# Connectors.net
KiCad netlist of a schematic drawn in Altium Designer
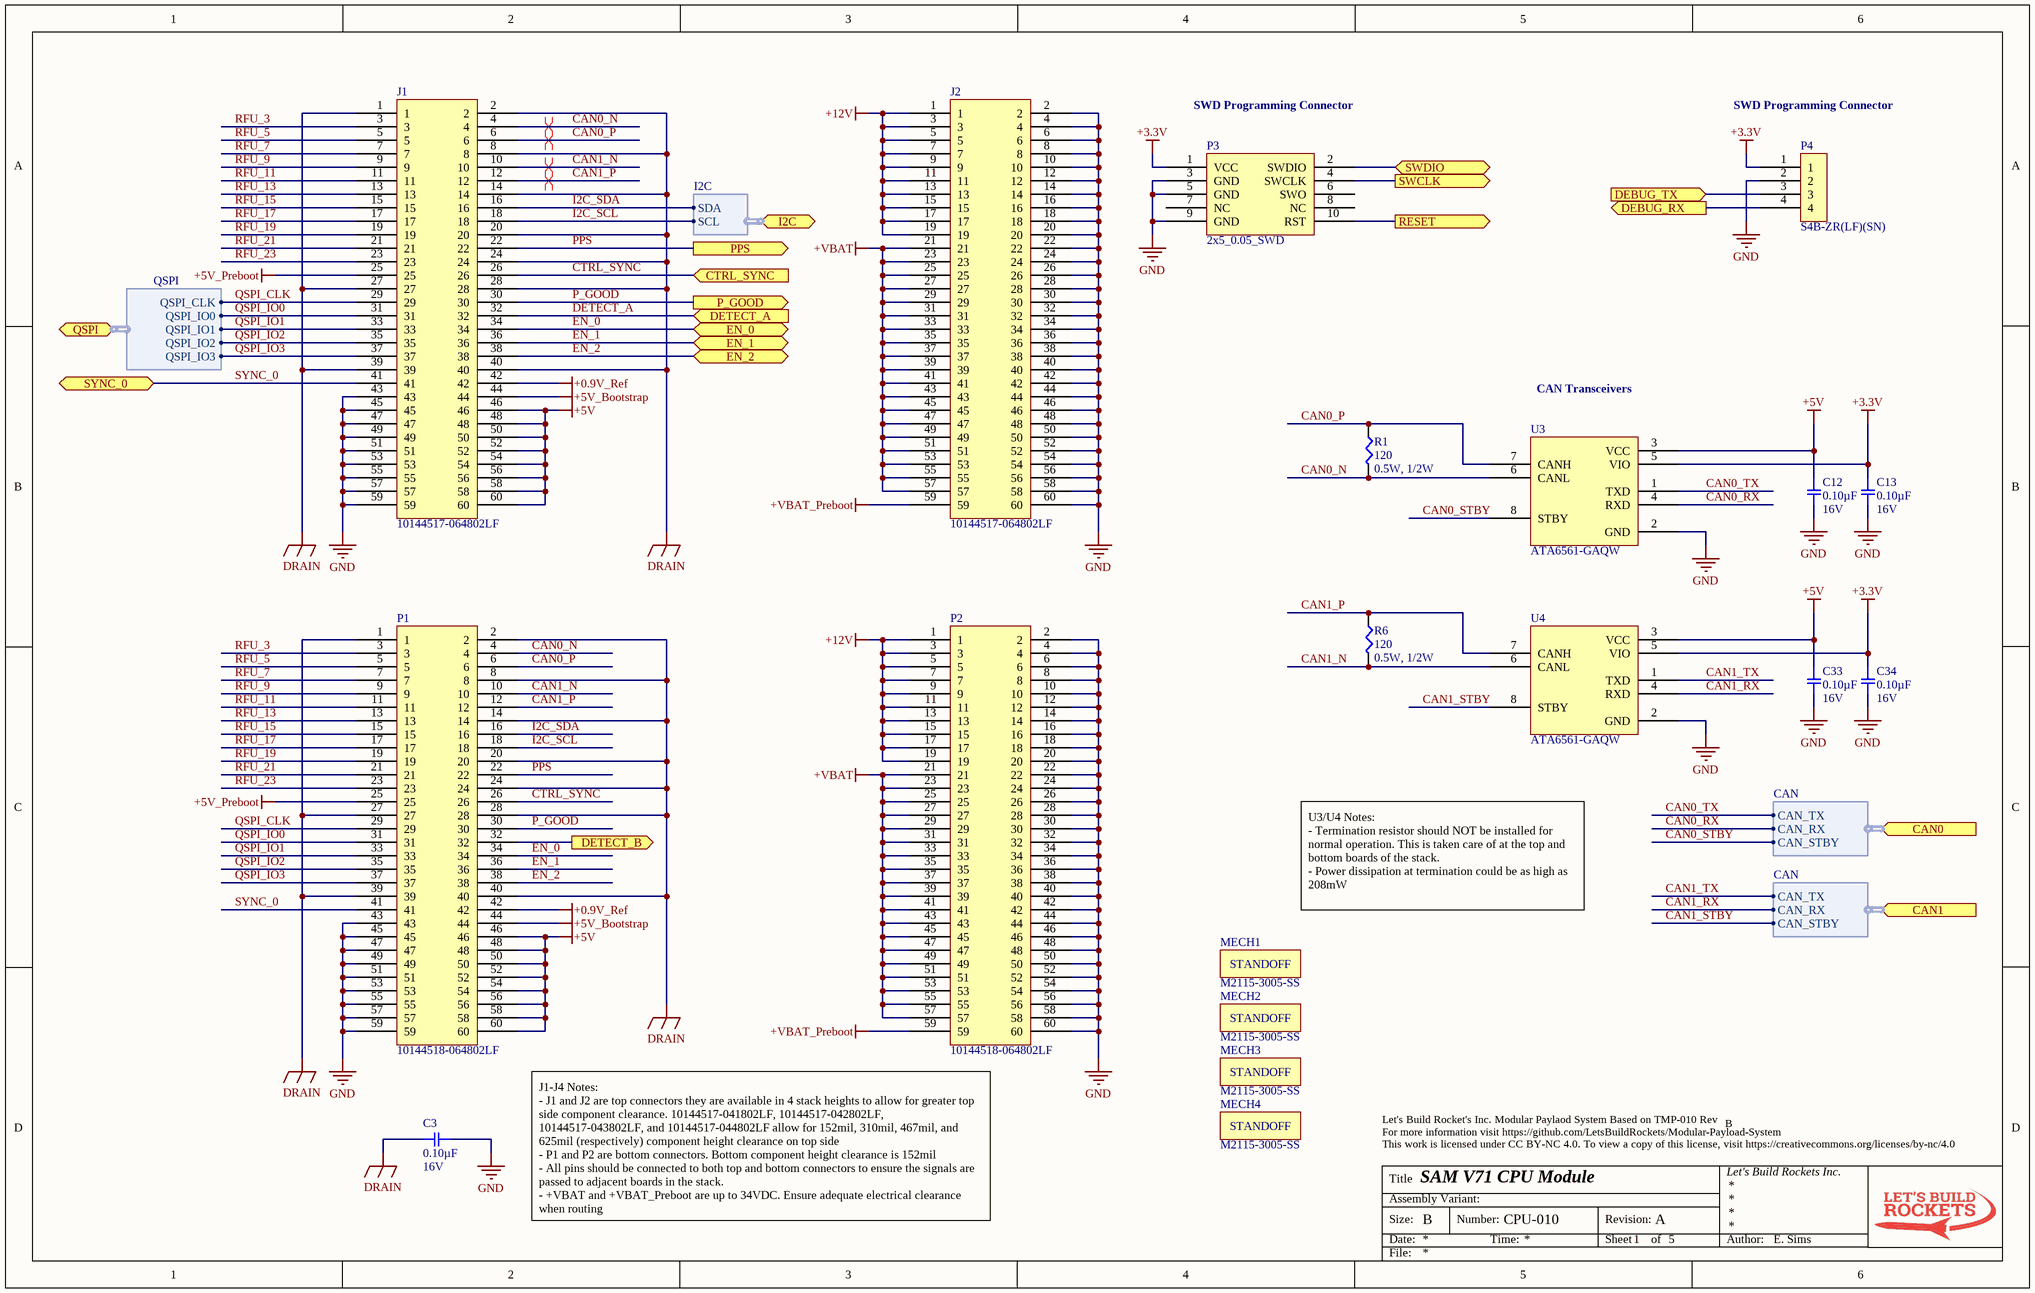
[diagram p0: Connectors.SchDoc]

(export (version "E")
  (design (tool "Eeschema 10.0.6"))
  (components
    (comp (ref "C3")
      (value "0.10µF")
      (footprint "SMD-0402C")
      (description "CAP CER 0.1UF 16V X7R 0402")
      (fields
        (field (name "DIGI-KEY PART NUMBER") "490-4759-1-ND")
        (field (name "PART NUMBER") "GCM155R71C104KA55D")
        (field (name "VOLTAGE") "16V")
      )
      (libsource (lib "capacitor_murata_0402") (part "GCM155R71C104KA55D"))
    )
    (comp (ref "C12")
      (value "0.10µF")
      (footprint "SMD-0402C")
      (description "CAP CER 0.1UF 16V X7R 0402")
      (fields
        (field (name "DIGI-KEY PART NUMBER") "490-4759-1-ND")
        (field (name "PART NUMBER") "GCM155R71C104KA55D")
        (field (name "VOLTAGE") "16V")
      )
      (libsource (lib "capacitor_murata_0402") (part "GCM155R71C104KA55D"))
    )
    (comp (ref "C13")
      (value "0.10µF")
      (footprint "SMD-0402C")
      (description "CAP CER 0.1UF 16V X7R 0402")
      (fields
        (field (name "DIGI-KEY PART NUMBER") "490-4759-1-ND")
        (field (name "PART NUMBER") "GCM155R71C104KA55D")
        (field (name "VOLTAGE") "16V")
      )
      (libsource (lib "capacitor_murata_0402") (part "GCM155R71C104KA55D"))
    )
    (comp (ref "C33")
      (value "0.10µF")
      (footprint "SMD-0402C")
      (description "CAP CER 0.1UF 16V X7R 0402")
      (fields
        (field (name "DIGI-KEY PART NUMBER") "490-4759-1-ND")
        (field (name "PART NUMBER") "GCM155R71C104KA55D")
        (field (name "VOLTAGE") "16V")
      )
      (libsource (lib "capacitor_murata_0402") (part "GCM155R71C104KA55D"))
    )
    (comp (ref "C34")
      (value "0.10µF")
      (footprint "SMD-0402C")
      (description "CAP CER 0.1UF 16V X7R 0402")
      (fields
        (field (name "DIGI-KEY PART NUMBER") "490-4759-1-ND")
        (field (name "PART NUMBER") "GCM155R71C104KA55D")
        (field (name "VOLTAGE") "16V")
      )
      (libsource (lib "capacitor_murata_0402") (part "GCM155R71C104KA55D"))
    )
    (comp (ref "J1")
      (value "10144517-064802LF")
      (footprint "10144517-064802LF")
      (libsource (lib "ModularPayload") (part "10144517-064802LF"))
    )
    (comp (ref "J2")
      (value "10144517-064802LF")
      (footprint "10144517-064802LF")
      (libsource (lib "ModularPayload") (part "10144517-064802LF"))
    )
    (comp (ref "MECH1")
      (value "M2115-3005-SS")
      (footprint "M2115-3005-SS")
      (libsource (lib "ModularPayload") (part "M2115-3005-SS"))
    )
    (comp (ref "MECH2")
      (value "M2115-3005-SS")
      (footprint "M2115-3005-SS")
      (libsource (lib "ModularPayload") (part "M2115-3005-SS"))
    )
    (comp (ref "MECH3")
      (value "M2115-3005-SS")
      (footprint "M2115-3005-SS")
      (libsource (lib "ModularPayload") (part "M2115-3005-SS"))
    )
    (comp (ref "MECH4")
      (value "M2115-3005-SS")
      (footprint "M2115-3005-SS")
      (libsource (lib "ModularPayload") (part "M2115-3005-SS"))
    )
    (comp (ref "P1")
      (value "10144518-064802LF")
      (footprint "10144518-064802LF")
      (libsource (lib "ModularPayload") (part "10144518-064802LF"))
    )
    (comp (ref "P2")
      (value "10144518-064802LF")
      (footprint "10144518-064802LF")
      (libsource (lib "ModularPayload") (part "10144518-064802LF"))
    )
    (comp (ref "P3")
      (value "2x5_0.05_SWD")
      (footprint "2x5_0.05_R")
      (libsource (lib "ModularPayload") (part "2x5_0.05_SWD"))
    )
    (comp (ref "P4")
      (value "S4B-ZR(LF)(SN)")
      (footprint "S4B-ZR(LF)(SN)")
      (libsource (lib "ModularPayload") (part "S4B-ZR(LF)(SN)"))
    )
    (comp (ref "R1")
      (value "120")
      (footprint "SMD-0805-RES")
      (description "RES SMD 120 OHM 5% 1/2W 0805")
      (fields
        (field (name "PART NUMBER") "ERJ-P6WJ121V")
        (field (name "DIGI-KEY PART NUMBER") "P16943CT-ND")
        (field (name "POWER (WATTS)") "0.5W, 1/2W")
      )
      (libsource (lib "Panasonic_ERJ_0805") (part "ERJ-P6WJ121V"))
    )
    (comp (ref "R6")
      (value "120")
      (footprint "SMD-0805-RES")
      (description "RES SMD 120 OHM 5% 1/2W 0805")
      (fields
        (field (name "PART NUMBER") "ERJ-P6WJ121V")
        (field (name "DIGI-KEY PART NUMBER") "P16943CT-ND")
        (field (name "POWER (WATTS)") "0.5W, 1/2W")
      )
      (libsource (lib "Panasonic_ERJ_0805") (part "ERJ-P6WJ121V"))
    )
    (comp (ref "U3")
      (value "ATA6561-GAQW")
      (footprint "SOIC127P600X175-8N")
      (libsource (lib "ModularPayload") (part "ATA6561-GAQW"))
    )
    (comp (ref "U4")
      (value "ATA6561-GAQW")
      (footprint "SOIC127P600X175-8N")
      (libsource (lib "ModularPayload") (part "ATA6561-GAQW"))
    )
  )
  (nets
    (net (code "4") (name "+0.9V_Ref") (class "Default")
      (node (ref "J1") (pin "42") (pinfunction "42_42") (pintype "passive"))
      (node (ref "P1") (pin "42") (pinfunction "42_42") (pintype "passive"))
    )
    (net (code "5") (name "+3.3V") (class "Default")
      (node (ref "C13") (pin "1") (pinfunction "1_1") (pintype "passive"))
      (node (ref "C34") (pin "1") (pinfunction "1_1") (pintype "passive"))
      (node (ref "P3") (pin "1") (pinfunction "VCC_1") (pintype "passive"))
      (node (ref "P4") (pin "1") (pinfunction "1_1") (pintype "passive"))
      (node (ref "U3") (pin "5") (pinfunction "VIO_5") (pintype "passive"))
      (node (ref "U4") (pin "5") (pinfunction "VIO_5") (pintype "passive"))
    )
    (net (code "6") (name "+5V") (class "Default")
      (node (ref "C12") (pin "1") (pinfunction "1_1") (pintype "passive"))
      (node (ref "C33") (pin "1") (pinfunction "1_1") (pintype "passive"))
      (node (ref "J1") (pin "46") (pinfunction "46_46") (pintype "passive"))
      (node (ref "J1") (pin "48") (pinfunction "48_48") (pintype "passive"))
      (node (ref "J1") (pin "50") (pinfunction "50_50") (pintype "passive"))
      (node (ref "J1") (pin "52") (pinfunction "52_52") (pintype "passive"))
      (node (ref "J1") (pin "54") (pinfunction "54_54") (pintype "passive"))
      (node (ref "J1") (pin "56") (pinfunction "56_56") (pintype "passive"))
      (node (ref "J1") (pin "58") (pinfunction "58_58") (pintype "passive"))
      (node (ref "J1") (pin "60") (pinfunction "60_60") (pintype "passive"))
      (node (ref "P1") (pin "46") (pinfunction "46_46") (pintype "passive"))
      (node (ref "P1") (pin "48") (pinfunction "48_48") (pintype "passive"))
      (node (ref "P1") (pin "50") (pinfunction "50_50") (pintype "passive"))
      (node (ref "P1") (pin "52") (pinfunction "52_52") (pintype "passive"))
      (node (ref "P1") (pin "54") (pinfunction "54_54") (pintype "passive"))
      (node (ref "P1") (pin "56") (pinfunction "56_56") (pintype "passive"))
      (node (ref "P1") (pin "58") (pinfunction "58_58") (pintype "passive"))
      (node (ref "P1") (pin "60") (pinfunction "60_60") (pintype "passive"))
      (node (ref "U3") (pin "3") (pinfunction "VCC_3") (pintype "passive"))
      (node (ref "U4") (pin "3") (pinfunction "VCC_3") (pintype "passive"))
    )
    (net (code "7") (name "+5V_Bootstrap") (class "Default")
      (node (ref "J1") (pin "44") (pinfunction "44_44") (pintype "passive"))
      (node (ref "P1") (pin "44") (pinfunction "44_44") (pintype "passive"))
    )
    (net (code "8") (name "+5V_Preboot") (class "Default")
      (node (ref "J1") (pin "25") (pinfunction "25_25") (pintype "passive"))
      (node (ref "P1") (pin "25") (pinfunction "25_25") (pintype "passive"))
    )
    (net (code "9") (name "+12V") (class "Default")
      (node (ref "J2") (pin "1") (pinfunction "1_1") (pintype "passive"))
      (node (ref "J2") (pin "11") (pinfunction "11_11") (pintype "passive"))
      (node (ref "J2") (pin "13") (pinfunction "13_13") (pintype "passive"))
      (node (ref "J2") (pin "15") (pinfunction "15_15") (pintype "passive"))
      (node (ref "J2") (pin "17") (pinfunction "17_17") (pintype "passive"))
      (node (ref "J2") (pin "19") (pinfunction "19_19") (pintype "passive"))
      (node (ref "J2") (pin "3") (pinfunction "3_3") (pintype "passive"))
      (node (ref "J2") (pin "5") (pinfunction "5_5") (pintype "passive"))
      (node (ref "J2") (pin "7") (pinfunction "7_7") (pintype "passive"))
      (node (ref "J2") (pin "9") (pinfunction "9_9") (pintype "passive"))
      (node (ref "P2") (pin "1") (pinfunction "1_1") (pintype "passive"))
      (node (ref "P2") (pin "11") (pinfunction "11_11") (pintype "passive"))
      (node (ref "P2") (pin "13") (pinfunction "13_13") (pintype "passive"))
      (node (ref "P2") (pin "15") (pinfunction "15_15") (pintype "passive"))
      (node (ref "P2") (pin "17") (pinfunction "17_17") (pintype "passive"))
      (node (ref "P2") (pin "19") (pinfunction "19_19") (pintype "passive"))
      (node (ref "P2") (pin "3") (pinfunction "3_3") (pintype "passive"))
      (node (ref "P2") (pin "5") (pinfunction "5_5") (pintype "passive"))
      (node (ref "P2") (pin "7") (pinfunction "7_7") (pintype "passive"))
      (node (ref "P2") (pin "9") (pinfunction "9_9") (pintype "passive"))
    )
    (net (code "10") (name "+VBAT") (class "Default")
      (node (ref "J2") (pin "21") (pinfunction "21_21") (pintype "passive"))
      (node (ref "J2") (pin "23") (pinfunction "23_23") (pintype "passive"))
      (node (ref "J2") (pin "25") (pinfunction "25_25") (pintype "passive"))
      (node (ref "J2") (pin "27") (pinfunction "27_27") (pintype "passive"))
      (node (ref "J2") (pin "29") (pinfunction "29_29") (pintype "passive"))
      (node (ref "J2") (pin "31") (pinfunction "31_31") (pintype "passive"))
      (node (ref "J2") (pin "33") (pinfunction "33_33") (pintype "passive"))
      (node (ref "J2") (pin "35") (pinfunction "35_35") (pintype "passive"))
      (node (ref "J2") (pin "37") (pinfunction "37_37") (pintype "passive"))
      (node (ref "J2") (pin "39") (pinfunction "39_39") (pintype "passive"))
      (node (ref "J2") (pin "41") (pinfunction "41_41") (pintype "passive"))
      (node (ref "J2") (pin "43") (pinfunction "43_43") (pintype "passive"))
      (node (ref "J2") (pin "45") (pinfunction "45_45") (pintype "passive"))
      (node (ref "J2") (pin "47") (pinfunction "47_47") (pintype "passive"))
      (node (ref "J2") (pin "49") (pinfunction "49_49") (pintype "passive"))
      (node (ref "J2") (pin "51") (pinfunction "51_51") (pintype "passive"))
      (node (ref "J2") (pin "53") (pinfunction "53_53") (pintype "passive"))
      (node (ref "J2") (pin "55") (pinfunction "55_55") (pintype "passive"))
      (node (ref "J2") (pin "57") (pinfunction "57_57") (pintype "passive"))
      (node (ref "P2") (pin "21") (pinfunction "21_21") (pintype "passive"))
      (node (ref "P2") (pin "23") (pinfunction "23_23") (pintype "passive"))
      (node (ref "P2") (pin "25") (pinfunction "25_25") (pintype "passive"))
      (node (ref "P2") (pin "27") (pinfunction "27_27") (pintype "passive"))
      (node (ref "P2") (pin "29") (pinfunction "29_29") (pintype "passive"))
      (node (ref "P2") (pin "31") (pinfunction "31_31") (pintype "passive"))
      (node (ref "P2") (pin "33") (pinfunction "33_33") (pintype "passive"))
      (node (ref "P2") (pin "35") (pinfunction "35_35") (pintype "passive"))
      (node (ref "P2") (pin "37") (pinfunction "37_37") (pintype "passive"))
      (node (ref "P2") (pin "39") (pinfunction "39_39") (pintype "passive"))
      (node (ref "P2") (pin "41") (pinfunction "41_41") (pintype "passive"))
      (node (ref "P2") (pin "43") (pinfunction "43_43") (pintype "passive"))
      (node (ref "P2") (pin "45") (pinfunction "45_45") (pintype "passive"))
      (node (ref "P2") (pin "47") (pinfunction "47_47") (pintype "passive"))
      (node (ref "P2") (pin "49") (pinfunction "49_49") (pintype "passive"))
      (node (ref "P2") (pin "51") (pinfunction "51_51") (pintype "passive"))
      (node (ref "P2") (pin "53") (pinfunction "53_53") (pintype "passive"))
      (node (ref "P2") (pin "55") (pinfunction "55_55") (pintype "passive"))
      (node (ref "P2") (pin "57") (pinfunction "57_57") (pintype "passive"))
    )
    (net (code "11") (name "+VBAT_Preboot") (class "Default")
      (node (ref "J2") (pin "59") (pinfunction "59_59") (pintype "passive"))
      (node (ref "P2") (pin "59") (pinfunction "59_59") (pintype "passive"))
    )
    (net (code "12") (name "/CAN0_N") (class "Default")
      (node (ref "J1") (pin "4") (pinfunction "4_4") (pintype "passive"))
      (node (ref "P1") (pin "4") (pinfunction "4_4") (pintype "passive"))
      (node (ref "R1") (pin "2") (pinfunction "2_2") (pintype "passive"))
      (node (ref "U3") (pin "6") (pinfunction "CANL_6") (pintype "passive"))
    )
    (net (code "13") (name "/CAN0_P") (class "Default")
      (node (ref "J1") (pin "6") (pinfunction "6_6") (pintype "passive"))
      (node (ref "P1") (pin "6") (pinfunction "6_6") (pintype "passive"))
      (node (ref "R1") (pin "1") (pinfunction "1_1") (pintype "passive"))
      (node (ref "U3") (pin "7") (pinfunction "CANH_7") (pintype "passive"))
    )
    (net (code "14") (name "/CAN0_RX") (class "Default")
      (node (ref "U3") (pin "4") (pinfunction "RXD_4") (pintype "passive"))
    )
    (net (code "15") (name "/CAN0_STBY") (class "Default")
      (node (ref "U3") (pin "8") (pinfunction "STBY_8") (pintype "passive"))
    )
    (net (code "16") (name "/CAN0_TX") (class "Default")
      (node (ref "U3") (pin "1") (pinfunction "TXD_1") (pintype "passive"))
    )
    (net (code "17") (name "/CAN1_N") (class "Default")
      (node (ref "J1") (pin "10") (pinfunction "10_10") (pintype "passive"))
      (node (ref "P1") (pin "10") (pinfunction "10_10") (pintype "passive"))
      (node (ref "R6") (pin "2") (pinfunction "2_2") (pintype "passive"))
      (node (ref "U4") (pin "6") (pinfunction "CANL_6") (pintype "passive"))
    )
    (net (code "18") (name "/CAN1_P") (class "Default")
      (node (ref "J1") (pin "12") (pinfunction "12_12") (pintype "passive"))
      (node (ref "P1") (pin "12") (pinfunction "12_12") (pintype "passive"))
      (node (ref "R6") (pin "1") (pinfunction "1_1") (pintype "passive"))
      (node (ref "U4") (pin "7") (pinfunction "CANH_7") (pintype "passive"))
    )
    (net (code "19") (name "/CAN1_RX") (class "Default")
      (node (ref "U4") (pin "4") (pinfunction "RXD_4") (pintype "passive"))
    )
    (net (code "20") (name "/CAN1_STBY") (class "Default")
      (node (ref "U4") (pin "8") (pinfunction "STBY_8") (pintype "passive"))
    )
    (net (code "21") (name "/CAN1_TX") (class "Default")
      (node (ref "U4") (pin "1") (pinfunction "TXD_1") (pintype "passive"))
    )
    (net (code "22") (name "/CTRL_SYNC") (class "Default")
      (node (ref "J1") (pin "26") (pinfunction "26_26") (pintype "passive"))
      (node (ref "P1") (pin "26") (pinfunction "26_26") (pintype "passive"))
    )
    (net (code "23") (name "/DEBUG_RX") (class "Default")
      (node (ref "P4") (pin "4") (pinfunction "4_4") (pintype "passive"))
    )
    (net (code "24") (name "/DEBUG_TX") (class "Default")
      (node (ref "P4") (pin "3") (pinfunction "3_3") (pintype "passive"))
    )
    (net (code "25") (name "/DETECT_A") (class "Default")
      (node (ref "J1") (pin "32") (pinfunction "32_32") (pintype "passive"))
    )
    (net (code "26") (name "/DETECT_B") (class "Default")
      (node (ref "P1") (pin "32") (pinfunction "32_32") (pintype "passive"))
    )
    (net (code "27") (name "/EN_0") (class "Default")
      (node (ref "J1") (pin "34") (pinfunction "34_34") (pintype "passive"))
      (node (ref "P1") (pin "34") (pinfunction "34_34") (pintype "passive"))
    )
    (net (code "28") (name "/EN_1") (class "Default")
      (node (ref "J1") (pin "36") (pinfunction "36_36") (pintype "passive"))
      (node (ref "P1") (pin "36") (pinfunction "36_36") (pintype "passive"))
    )
    (net (code "29") (name "/EN_2") (class "Default")
      (node (ref "J1") (pin "38") (pinfunction "38_38") (pintype "passive"))
      (node (ref "P1") (pin "38") (pinfunction "38_38") (pintype "passive"))
    )
    (net (code "30") (name "/I2C_SCL") (class "Default")
      (node (ref "J1") (pin "18") (pinfunction "18_18") (pintype "passive"))
      (node (ref "P1") (pin "18") (pinfunction "18_18") (pintype "passive"))
    )
    (net (code "31") (name "/I2C_SDA") (class "Default")
      (node (ref "J1") (pin "16") (pinfunction "16_16") (pintype "passive"))
      (node (ref "P1") (pin "16") (pinfunction "16_16") (pintype "passive"))
    )
    (net (code "32") (name "/PPS") (class "Default")
      (node (ref "J1") (pin "22") (pinfunction "22_22") (pintype "passive"))
      (node (ref "P1") (pin "22") (pinfunction "22_22") (pintype "passive"))
    )
    (net (code "33") (name "/P_GOOD") (class "Default")
      (node (ref "J1") (pin "30") (pinfunction "30_30") (pintype "passive"))
      (node (ref "P1") (pin "30") (pinfunction "30_30") (pintype "passive"))
    )
    (net (code "34") (name "/QSPI_CLK") (class "Default")
      (node (ref "J1") (pin "29") (pinfunction "29_29") (pintype "passive"))
      (node (ref "P1") (pin "29") (pinfunction "29_29") (pintype "passive"))
    )
    (net (code "35") (name "/QSPI_IO0") (class "Default")
      (node (ref "J1") (pin "31") (pinfunction "31_31") (pintype "passive"))
      (node (ref "P1") (pin "31") (pinfunction "31_31") (pintype "passive"))
    )
    (net (code "36") (name "/QSPI_IO1") (class "Default")
      (node (ref "J1") (pin "33") (pinfunction "33_33") (pintype "passive"))
      (node (ref "P1") (pin "33") (pinfunction "33_33") (pintype "passive"))
    )
    (net (code "37") (name "/QSPI_IO2") (class "Default")
      (node (ref "J1") (pin "35") (pinfunction "35_35") (pintype "passive"))
      (node (ref "P1") (pin "35") (pinfunction "35_35") (pintype "passive"))
    )
    (net (code "38") (name "/QSPI_IO3") (class "Default")
      (node (ref "J1") (pin "37") (pinfunction "37_37") (pintype "passive"))
      (node (ref "P1") (pin "37") (pinfunction "37_37") (pintype "passive"))
    )
    (net (code "39") (name "/RESET") (class "Default")
      (node (ref "P3") (pin "10") (pinfunction "RST_10") (pintype "passive"))
    )
    (net (code "40") (name "/RFU_3") (class "Default")
      (node (ref "J1") (pin "3") (pinfunction "3_3") (pintype "passive"))
      (node (ref "P1") (pin "3") (pinfunction "3_3") (pintype "passive"))
    )
    (net (code "41") (name "/RFU_5") (class "Default")
      (node (ref "J1") (pin "5") (pinfunction "5_5") (pintype "passive"))
      (node (ref "P1") (pin "5") (pinfunction "5_5") (pintype "passive"))
    )
    (net (code "42") (name "/RFU_7") (class "Default")
      (node (ref "J1") (pin "7") (pinfunction "7_7") (pintype "passive"))
      (node (ref "P1") (pin "7") (pinfunction "7_7") (pintype "passive"))
    )
    (net (code "43") (name "/RFU_9") (class "Default")
      (node (ref "J1") (pin "9") (pinfunction "9_9") (pintype "passive"))
      (node (ref "P1") (pin "9") (pinfunction "9_9") (pintype "passive"))
    )
    (net (code "44") (name "/RFU_11") (class "Default")
      (node (ref "J1") (pin "11") (pinfunction "11_11") (pintype "passive"))
      (node (ref "P1") (pin "11") (pinfunction "11_11") (pintype "passive"))
    )
    (net (code "45") (name "/RFU_13") (class "Default")
      (node (ref "J1") (pin "13") (pinfunction "13_13") (pintype "passive"))
      (node (ref "P1") (pin "13") (pinfunction "13_13") (pintype "passive"))
    )
    (net (code "46") (name "/RFU_15") (class "Default")
      (node (ref "J1") (pin "15") (pinfunction "15_15") (pintype "passive"))
      (node (ref "P1") (pin "15") (pinfunction "15_15") (pintype "passive"))
    )
    (net (code "47") (name "/RFU_17") (class "Default")
      (node (ref "J1") (pin "17") (pinfunction "17_17") (pintype "passive"))
      (node (ref "P1") (pin "17") (pinfunction "17_17") (pintype "passive"))
    )
    (net (code "48") (name "/RFU_19") (class "Default")
      (node (ref "J1") (pin "19") (pinfunction "19_19") (pintype "passive"))
      (node (ref "P1") (pin "19") (pinfunction "19_19") (pintype "passive"))
    )
    (net (code "49") (name "/RFU_21") (class "Default")
      (node (ref "J1") (pin "21") (pinfunction "21_21") (pintype "passive"))
      (node (ref "P1") (pin "21") (pinfunction "21_21") (pintype "passive"))
    )
    (net (code "50") (name "/RFU_23") (class "Default")
      (node (ref "J1") (pin "23") (pinfunction "23_23") (pintype "passive"))
      (node (ref "P1") (pin "23") (pinfunction "23_23") (pintype "passive"))
    )
    (net (code "51") (name "/SWCLK") (class "Default")
      (node (ref "P3") (pin "4") (pinfunction "SWCLK_4") (pintype "passive"))
    )
    (net (code "52") (name "/SWDIO") (class "Default")
      (node (ref "P3") (pin "2") (pinfunction "SWDIO_2") (pintype "passive"))
    )
    (net (code "53") (name "/SYNC_0") (class "Default")
      (node (ref "J1") (pin "41") (pinfunction "41_41") (pintype "passive"))
      (node (ref "P1") (pin "41") (pinfunction "41_41") (pintype "passive"))
    )
    (net (code "57") (name "DRAIN") (class "Default")
      (node (ref "C3") (pin "2") (pinfunction "2_2") (pintype "passive"))
      (node (ref "J1") (pin "1") (pinfunction "1_1") (pintype "passive"))
      (node (ref "J1") (pin "14") (pinfunction "14_14") (pintype "passive"))
      (node (ref "J1") (pin "2") (pinfunction "2_2") (pintype "passive"))
      (node (ref "J1") (pin "20") (pinfunction "20_20") (pintype "passive"))
      (node (ref "J1") (pin "24") (pinfunction "24_24") (pintype "passive"))
      (node (ref "J1") (pin "27") (pinfunction "27_27") (pintype "passive"))
      (node (ref "J1") (pin "28") (pinfunction "28_28") (pintype "passive"))
      (node (ref "J1") (pin "39") (pinfunction "39_39") (pintype "passive"))
      (node (ref "J1") (pin "40") (pinfunction "40_40") (pintype "passive"))
      (node (ref "J1") (pin "8") (pinfunction "8_8") (pintype "passive"))
      (node (ref "P1") (pin "1") (pinfunction "1_1") (pintype "passive"))
      (node (ref "P1") (pin "14") (pinfunction "14_14") (pintype "passive"))
      (node (ref "P1") (pin "2") (pinfunction "2_2") (pintype "passive"))
      (node (ref "P1") (pin "20") (pinfunction "20_20") (pintype "passive"))
      (node (ref "P1") (pin "24") (pinfunction "24_24") (pintype "passive"))
      (node (ref "P1") (pin "27") (pinfunction "27_27") (pintype "passive"))
      (node (ref "P1") (pin "28") (pinfunction "28_28") (pintype "passive"))
      (node (ref "P1") (pin "39") (pinfunction "39_39") (pintype "passive"))
      (node (ref "P1") (pin "40") (pinfunction "40_40") (pintype "passive"))
      (node (ref "P1") (pin "8") (pinfunction "8_8") (pintype "passive"))
    )
    (net (code "58") (name "GND") (class "Default")
      (node (ref "C12") (pin "2") (pinfunction "2_2") (pintype "passive"))
      (node (ref "C13") (pin "2") (pinfunction "2_2") (pintype "passive"))
      (node (ref "C3") (pin "1") (pinfunction "1_1") (pintype "passive"))
      (node (ref "C33") (pin "2") (pinfunction "2_2") (pintype "passive"))
      (node (ref "C34") (pin "2") (pinfunction "2_2") (pintype "passive"))
      (node (ref "J1") (pin "43") (pinfunction "43_43") (pintype "passive"))
      (node (ref "J1") (pin "45") (pinfunction "45_45") (pintype "passive"))
      (node (ref "J1") (pin "47") (pinfunction "47_47") (pintype "passive"))
      (node (ref "J1") (pin "49") (pinfunction "49_49") (pintype "passive"))
      (node (ref "J1") (pin "51") (pinfunction "51_51") (pintype "passive"))
      (node (ref "J1") (pin "53") (pinfunction "53_53") (pintype "passive"))
      (node (ref "J1") (pin "55") (pinfunction "55_55") (pintype "passive"))
      (node (ref "J1") (pin "57") (pinfunction "57_57") (pintype "passive"))
      (node (ref "J1") (pin "59") (pinfunction "59_59") (pintype "passive"))
      (node (ref "J2") (pin "10") (pinfunction "10_10") (pintype "passive"))
      (node (ref "J2") (pin "12") (pinfunction "12_12") (pintype "passive"))
      (node (ref "J2") (pin "14") (pinfunction "14_14") (pintype "passive"))
      (node (ref "J2") (pin "16") (pinfunction "16_16") (pintype "passive"))
      (node (ref "J2") (pin "18") (pinfunction "18_18") (pintype "passive"))
      (node (ref "J2") (pin "2") (pinfunction "2_2") (pintype "passive"))
      (node (ref "J2") (pin "20") (pinfunction "20_20") (pintype "passive"))
      (node (ref "J2") (pin "22") (pinfunction "22_22") (pintype "passive"))
      (node (ref "J2") (pin "24") (pinfunction "24_24") (pintype "passive"))
      (node (ref "J2") (pin "26") (pinfunction "26_26") (pintype "passive"))
      (node (ref "J2") (pin "28") (pinfunction "28_28") (pintype "passive"))
      (node (ref "J2") (pin "30") (pinfunction "30_30") (pintype "passive"))
      (node (ref "J2") (pin "32") (pinfunction "32_32") (pintype "passive"))
      (node (ref "J2") (pin "34") (pinfunction "34_34") (pintype "passive"))
      (node (ref "J2") (pin "36") (pinfunction "36_36") (pintype "passive"))
      (node (ref "J2") (pin "38") (pinfunction "38_38") (pintype "passive"))
      (node (ref "J2") (pin "4") (pinfunction "4_4") (pintype "passive"))
      (node (ref "J2") (pin "40") (pinfunction "40_40") (pintype "passive"))
      (node (ref "J2") (pin "42") (pinfunction "42_42") (pintype "passive"))
      (node (ref "J2") (pin "44") (pinfunction "44_44") (pintype "passive"))
      (node (ref "J2") (pin "46") (pinfunction "46_46") (pintype "passive"))
      (node (ref "J2") (pin "48") (pinfunction "48_48") (pintype "passive"))
      (node (ref "J2") (pin "50") (pinfunction "50_50") (pintype "passive"))
      (node (ref "J2") (pin "52") (pinfunction "52_52") (pintype "passive"))
      (node (ref "J2") (pin "54") (pinfunction "54_54") (pintype "passive"))
      (node (ref "J2") (pin "56") (pinfunction "56_56") (pintype "passive"))
      (node (ref "J2") (pin "58") (pinfunction "58_58") (pintype "passive"))
      (node (ref "J2") (pin "6") (pinfunction "6_6") (pintype "passive"))
      (node (ref "J2") (pin "60") (pinfunction "60_60") (pintype "passive"))
      (node (ref "J2") (pin "8") (pinfunction "8_8") (pintype "passive"))
      (node (ref "P1") (pin "43") (pinfunction "43_43") (pintype "passive"))
      (node (ref "P1") (pin "45") (pinfunction "45_45") (pintype "passive"))
      (node (ref "P1") (pin "47") (pinfunction "47_47") (pintype "passive"))
      (node (ref "P1") (pin "49") (pinfunction "49_49") (pintype "passive"))
      (node (ref "P1") (pin "51") (pinfunction "51_51") (pintype "passive"))
      (node (ref "P1") (pin "53") (pinfunction "53_53") (pintype "passive"))
      (node (ref "P1") (pin "55") (pinfunction "55_55") (pintype "passive"))
      (node (ref "P1") (pin "57") (pinfunction "57_57") (pintype "passive"))
      (node (ref "P1") (pin "59") (pinfunction "59_59") (pintype "passive"))
      (node (ref "P2") (pin "10") (pinfunction "10_10") (pintype "passive"))
      (node (ref "P2") (pin "12") (pinfunction "12_12") (pintype "passive"))
      (node (ref "P2") (pin "14") (pinfunction "14_14") (pintype "passive"))
      (node (ref "P2") (pin "16") (pinfunction "16_16") (pintype "passive"))
      (node (ref "P2") (pin "18") (pinfunction "18_18") (pintype "passive"))
      (node (ref "P2") (pin "2") (pinfunction "2_2") (pintype "passive"))
      (node (ref "P2") (pin "20") (pinfunction "20_20") (pintype "passive"))
      (node (ref "P2") (pin "22") (pinfunction "22_22") (pintype "passive"))
      (node (ref "P2") (pin "24") (pinfunction "24_24") (pintype "passive"))
      (node (ref "P2") (pin "26") (pinfunction "26_26") (pintype "passive"))
      (node (ref "P2") (pin "28") (pinfunction "28_28") (pintype "passive"))
      (node (ref "P2") (pin "30") (pinfunction "30_30") (pintype "passive"))
      (node (ref "P2") (pin "32") (pinfunction "32_32") (pintype "passive"))
      (node (ref "P2") (pin "34") (pinfunction "34_34") (pintype "passive"))
      (node (ref "P2") (pin "36") (pinfunction "36_36") (pintype "passive"))
      (node (ref "P2") (pin "38") (pinfunction "38_38") (pintype "passive"))
      (node (ref "P2") (pin "4") (pinfunction "4_4") (pintype "passive"))
      (node (ref "P2") (pin "40") (pinfunction "40_40") (pintype "passive"))
      (node (ref "P2") (pin "42") (pinfunction "42_42") (pintype "passive"))
      (node (ref "P2") (pin "44") (pinfunction "44_44") (pintype "passive"))
      (node (ref "P2") (pin "46") (pinfunction "46_46") (pintype "passive"))
      (node (ref "P2") (pin "48") (pinfunction "48_48") (pintype "passive"))
      (node (ref "P2") (pin "50") (pinfunction "50_50") (pintype "passive"))
      (node (ref "P2") (pin "52") (pinfunction "52_52") (pintype "passive"))
      (node (ref "P2") (pin "54") (pinfunction "54_54") (pintype "passive"))
      (node (ref "P2") (pin "56") (pinfunction "56_56") (pintype "passive"))
      (node (ref "P2") (pin "58") (pinfunction "58_58") (pintype "passive"))
      (node (ref "P2") (pin "6") (pinfunction "6_6") (pintype "passive"))
      (node (ref "P2") (pin "60") (pinfunction "60_60") (pintype "passive"))
      (node (ref "P2") (pin "8") (pinfunction "8_8") (pintype "passive"))
      (node (ref "P3") (pin "3") (pinfunction "GND_3") (pintype "passive"))
      (node (ref "P3") (pin "5") (pinfunction "GND_5") (pintype "passive"))
      (node (ref "P3") (pin "9") (pinfunction "GND_9") (pintype "passive"))
      (node (ref "P4") (pin "2") (pinfunction "2_2") (pintype "passive"))
      (node (ref "U3") (pin "2") (pinfunction "GND_2") (pintype "passive"))
      (node (ref "U4") (pin "2") (pinfunction "GND_2") (pintype "passive"))
    )
    (net (code "59") (name "unconnected-(P3-NC-Pad7)") (class "Default")
      (node (ref "P3") (pin "7") (pinfunction "NC_7") (pintype "passive"))
    )
    (net (code "60") (name "unconnected-(P3-NC-Pad8)") (class "Default")
      (node (ref "P3") (pin "8") (pinfunction "NC_8") (pintype "passive"))
    )
    (net (code "61") (name "unconnected-(P3-SWO-Pad6)") (class "Default")
      (node (ref "P3") (pin "6") (pinfunction "SWO_6") (pintype "passive"))
    )
  )
)
